# Tiny_Arduino_Sch.net
KiCad netlist of a schematic drawn in Altium Designer
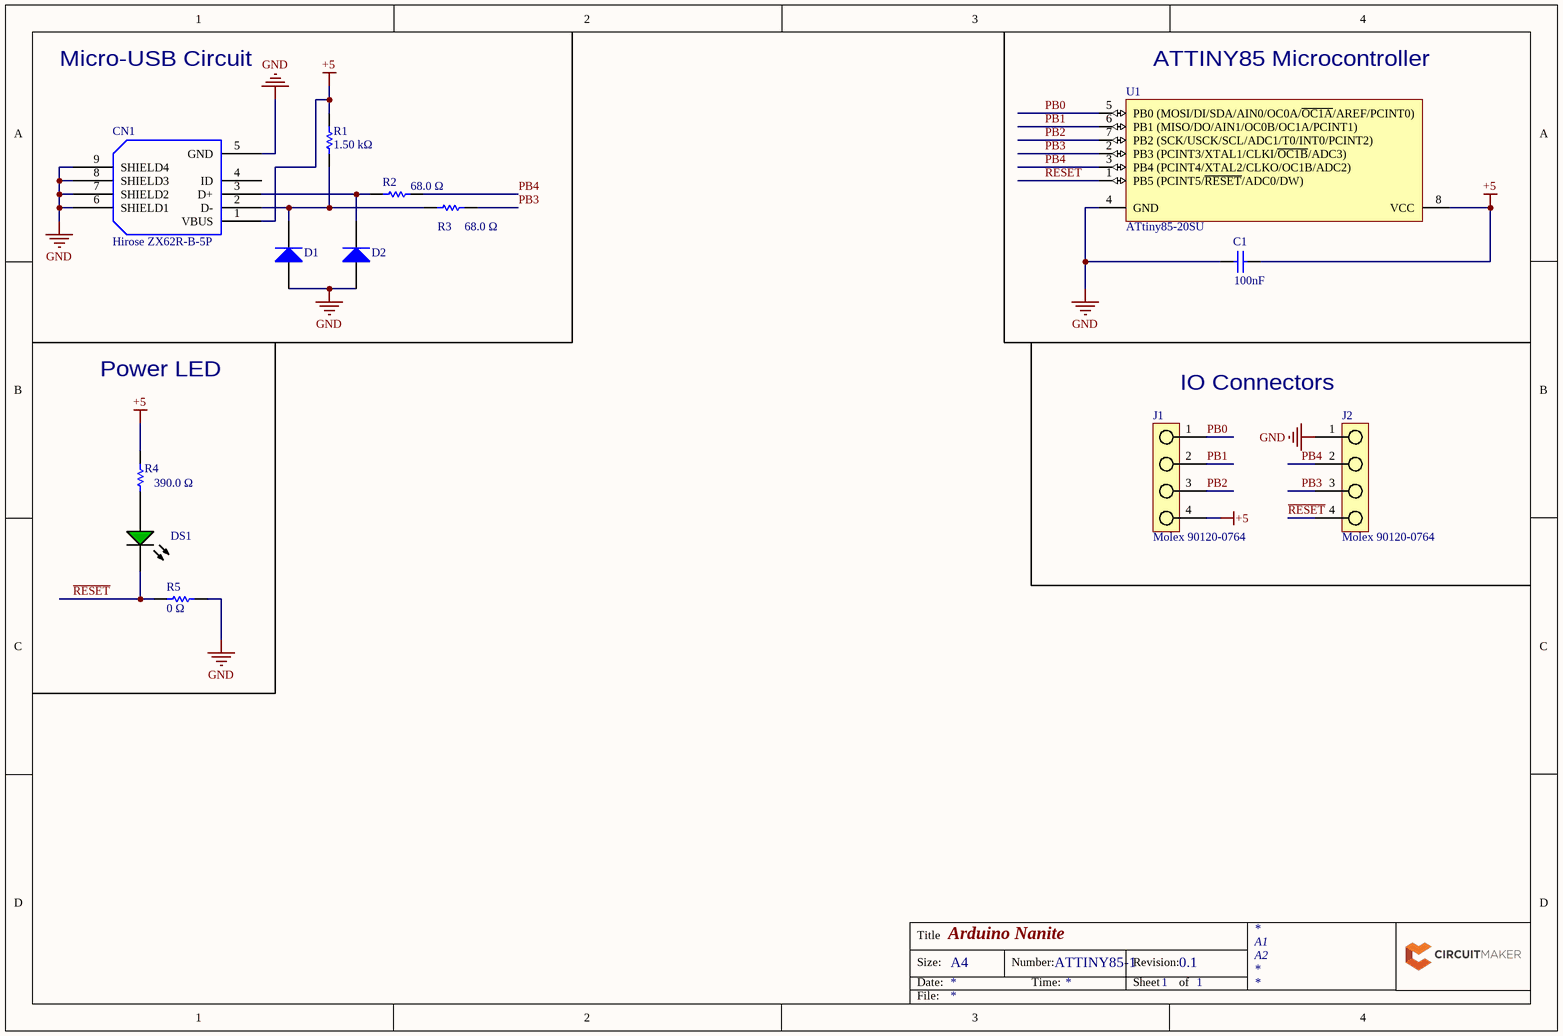
[diagram p0: Tiny_Arduino_Sch.SchDoc]

(export (version "E")
  (design (tool "Eeschema 10.0.6"))
  (components
    (comp (ref "C1")
      (value "AVX Interconnect / Elco 06033C104JAT2A")
      (footprint "CAPC1608X90X35LL15T15")
      (description "CAP CER 0.1UF 25V 5% X7R 0603")
      (fields (field (name "MANUFACTURER PART NUMBER") "06033C104JAT2A") (field (name "CAPACITANCE") "100nF"))
      (libsource (lib "CommunityVault") (part "CMP-19299432-4"))
    )
    (comp (ref "CN1")
      (value "Hirose ZX62R-B-5P")
      (footprint "PCB-kuo5gykd7jvbo0o0jro3-1")
      (fields (field (name "MANUFACTURER PART NUMBER") "ZX62R-B-5P"))
      (libsource (lib "Octopart library") (part "SYM-d224198bdd290de3-1"))
    )
    (comp (ref "D1")
      (value "Panasonic DB2J40700L")
      (footprint "PCB-2omd1n8vppfni68elkoq-1")
      (description "Sc, Schottky Barrier Diode / Single, For Rectification, Vr: 40v, If: 500ma")
      (fields (field (name "MANUFACTURER PART NUMBER") "DB2J40700L"))
      (libsource (lib "CommunityVault") (part "CMP-6124aa8bc752bee3-1"))
    )
    (comp (ref "D2")
      (value "Panasonic DB2J40700L")
      (footprint "PCB-2omd1n8vppfni68elkoq-1")
      (description "Sc, Schottky Barrier Diode / Single, For Rectification, Vr: 40v, If: 500ma")
      (fields (field (name "MANUFACTURER PART NUMBER") "DB2J40700L"))
      (libsource (lib "CommunityVault") (part "CMP-6124aa8bc752bee3-1"))
    )
    (comp (ref "DS1")
      (value "Vishay Semiconductor TLMG1100-GS08")
      (footprint "VSH-TLMX1100")
      (description "LED 0603 ULTRA BRIGHT GRN 35MCD")
      (fields (field (name "MANUFACTURER PART NUMBER") "TLMG1100-GS08"))
      (libsource (lib "CommunityVault") (part "CMP-1544807-2"))
    )
    (comp (ref "J1")
      (value "Molex 90120-0764")
      (footprint "PCB-mruwntkvy73mrw75dg9m-1")
      (fields (field (name "MANUFACTURER PART NUMBER") "90120-0764"))
      (libsource (lib "Octopart library") (part "SYM-f5c93cc9d0ed2a0e-2"))
    )
    (comp (ref "J2")
      (value "Molex 90120-0764")
      (footprint "PCB-mruwntkvy73mrw75dg9m-1")
      (fields (field (name "MANUFACTURER PART NUMBER") "90120-0764"))
      (libsource (lib "") (part "SYM-f5c93cc9d0ed2a0e-2_1"))
    )
    (comp (ref "R1")
      (value "Panasonic / Panasonic ECG ERJ-3EKF1501V")
      (footprint "0603R")
      (description "Res Thick Film 0603 1.5K Ohm 1% 0.1W(1/10W) ??100ppm/??C Molded SMD Automotive T/R")
      (fields (field (name "MANUFACTURER PART NUMBER") "ERJ-3EKF1501V") (field (name "RESISTANCE") "1.50 kΩ"))
      (libsource (lib "CommunityVault") (part "CMP-3653708-3"))
    )
    (comp (ref "R2")
      (value "Panasonic ERJ-3GEYJ680V")
      (footprint "RESC1608X55X30LL15T15")
      (description "RES SMD 68 OHM 5% 1/10W 0603")
      (fields (field (name "MANUFACTURER PART NUMBER") "ERJ-3GEYJ680V") (field (name "RESISTANCE") "68.0 Ω"))
      (libsource (lib "CommunityVault") (part "CMP-3708367-2"))
    )
    (comp (ref "R3")
      (value "Panasonic ERJ-3GEYJ680V")
      (footprint "RESC1608X55X30LL15T15")
      (description "RES SMD 68 OHM 5% 1/10W 0603")
      (fields (field (name "MANUFACTURER PART NUMBER") "ERJ-3GEYJ680V") (field (name "RESISTANCE") "68.0 Ω"))
      (libsource (lib "CommunityVault") (part "CMP-3708367-2"))
    )
    (comp (ref "R4")
      (value "Panasonic ERJ-3GEYJ391V")
      (footprint "RESC1608X55X30LL15T15")
      (description "Thick Film Resistors - SMD 0603 390ohms 5% Tol")
      (fields (field (name "MANUFACTURER PART NUMBER") "ERJ-3GEYJ391V") (field (name "RESISTANCE") "390.0 Ω"))
      (libsource (lib "CommunityVault") (part "CMP-3653665-2"))
    )
    (comp (ref "R5")
      (value "0 Ω")
      (footprint "RESC1608X05N")
      (description "RCA Series 0603 0.1 W 0 O Jumper Surface Mount Thick Film Chip Resistor")
      (fields (field (name "MANUFACTURER PART NUMBER") "RCA06030000ZSEA"))
      (libsource (lib "CommunityVault") (part "CMP-31acf99032f6ee6b-1"))
    )
    (comp (ref "U1")
      (value "ATtiny85-20SU")
      (footprint "8S2_L")
      (fields (field (name "MANUFACTURER PART NUMBER") "ATTINY85-20SU"))
      (libsource (lib "Octopart library") (part "MC-8B-ATT25-IL8"))
    )
  )
  (nets
    (net (code "1") (name "+5") (class "Default")
      (node (ref "C1") (pin "2") (pinfunction "2_2") (pintype "passive"))
      (node (ref "CN1") (pin "1") (pinfunction "VBUS_1") (pintype "passive"))
      (node (ref "J1") (pin "4") (pinfunction "4_4") (pintype "passive"))
      (node (ref "R1") (pin "2") (pinfunction "2_2") (pintype "passive"))
      (node (ref "R4") (pin "2") (pinfunction "2_2") (pintype "passive"))
      (node (ref "U1") (pin "8") (pinfunction "VCC_8") (pintype "power_in"))
    )
    (net (code "2") (name "/PB0") (class "Default")
      (node (ref "J1") (pin "1") (pinfunction "1_1") (pintype "passive"))
      (node (ref "U1") (pin "5") (pinfunction "PB0_(MOSI/DI/SDA/AIN0/OC0A/~{OC1A}/AREF/PCINT0)_5") (pintype "bidirectional"))
    )
    (net (code "3") (name "/PB1") (class "Default")
      (node (ref "J1") (pin "2") (pinfunction "2_2") (pintype "passive"))
      (node (ref "U1") (pin "6") (pinfunction "PB1_(MISO/DO/AIN1/OC0B/OC1A/PCINT1)_6") (pintype "bidirectional"))
    )
    (net (code "4") (name "/PB2") (class "Default")
      (node (ref "J1") (pin "3") (pinfunction "3_3") (pintype "passive"))
      (node (ref "U1") (pin "7") (pinfunction "PB2_(SCK/USCK/SCL/ADC1/T0/INT0/PCINT2)_7") (pintype "bidirectional"))
    )
    (net (code "5") (name "/PB3") (class "Default")
      (node (ref "J2") (pin "3") (pinfunction "3_3") (pintype "passive"))
      (node (ref "R3") (pin "2") (pinfunction "2_2") (pintype "passive"))
      (node (ref "U1") (pin "2") (pinfunction "PB3_(PCINT3/XTAL1/CLKI/~{OC1B}/ADC3)_2") (pintype "bidirectional"))
    )
    (net (code "6") (name "/PB4") (class "Default")
      (node (ref "J2") (pin "2") (pinfunction "2_2") (pintype "passive"))
      (node (ref "R2") (pin "2") (pinfunction "2_2") (pintype "passive"))
      (node (ref "U1") (pin "3") (pinfunction "PB4_(PCINT4/XTAL2/CLKO/OC1B/ADC2)_3") (pintype "bidirectional"))
    )
    (net (code "7") (name "/~{RESET}") (class "Default")
      (node (ref "DS1") (pin "2") (pinfunction "K_2") (pintype "passive"))
      (node (ref "J2") (pin "4") (pinfunction "4_4") (pintype "passive"))
      (node (ref "R5") (pin "1") (pinfunction "1_1") (pintype "passive"))
      (node (ref "U1") (pin "1") (pinfunction "PB5_(PCINT5/~{RESET}/ADC0/DW)_1") (pintype "bidirectional"))
    )
    (net (code "8") (name "GND") (class "Default")
      (node (ref "C1") (pin "1") (pinfunction "1_1") (pintype "passive"))
      (node (ref "CN1") (pin "5") (pinfunction "GND_5") (pintype "passive"))
      (node (ref "CN1") (pin "6") (pinfunction "SHIELD1_6") (pintype "passive"))
      (node (ref "CN1") (pin "7") (pinfunction "SHIELD2_7") (pintype "passive"))
      (node (ref "CN1") (pin "8") (pinfunction "SHIELD3_8") (pintype "passive"))
      (node (ref "CN1") (pin "9") (pinfunction "SHIELD4_9") (pintype "passive"))
      (node (ref "D1") (pin "1") (pinfunction "A_1") (pintype "passive"))
      (node (ref "D2") (pin "1") (pinfunction "A_1") (pintype "passive"))
      (node (ref "J2") (pin "1") (pinfunction "1_1") (pintype "passive"))
      (node (ref "R5") (pin "2") (pinfunction "2_2") (pintype "passive"))
      (node (ref "U1") (pin "4") (pinfunction "GND_4") (pintype "power_in"))
    )
    (net (code "9") (name "Net-(CN1-D+)") (class "Default")
      (node (ref "CN1") (pin "3") (pinfunction "D+_3") (pintype "passive"))
      (node (ref "D2") (pin "2") (pinfunction "K_2") (pintype "passive"))
      (node (ref "R2") (pin "1") (pinfunction "1_1") (pintype "passive"))
    )
    (net (code "10") (name "Net-(CN1-D-)") (class "Default")
      (node (ref "CN1") (pin "2") (pinfunction "D-_2") (pintype "passive"))
      (node (ref "D1") (pin "2") (pinfunction "K_2") (pintype "passive"))
      (node (ref "R1") (pin "1") (pinfunction "1_1") (pintype "passive"))
      (node (ref "R3") (pin "1") (pinfunction "1_1") (pintype "passive"))
    )
    (net (code "11") (name "Net-(DS1-A)") (class "Default")
      (node (ref "DS1") (pin "1") (pinfunction "A_1") (pintype "passive"))
      (node (ref "R4") (pin "1") (pinfunction "1_1") (pintype "passive"))
    )
    (net (code "12") (name "unconnected-(CN1-ID-Pad4)") (class "Default")
      (node (ref "CN1") (pin "4") (pinfunction "ID_4") (pintype "passive"))
    )
  )
)
